# Serial_CAN_Bus_V1_1.net
KiCad netlist of a schematic drawn in EAGLE
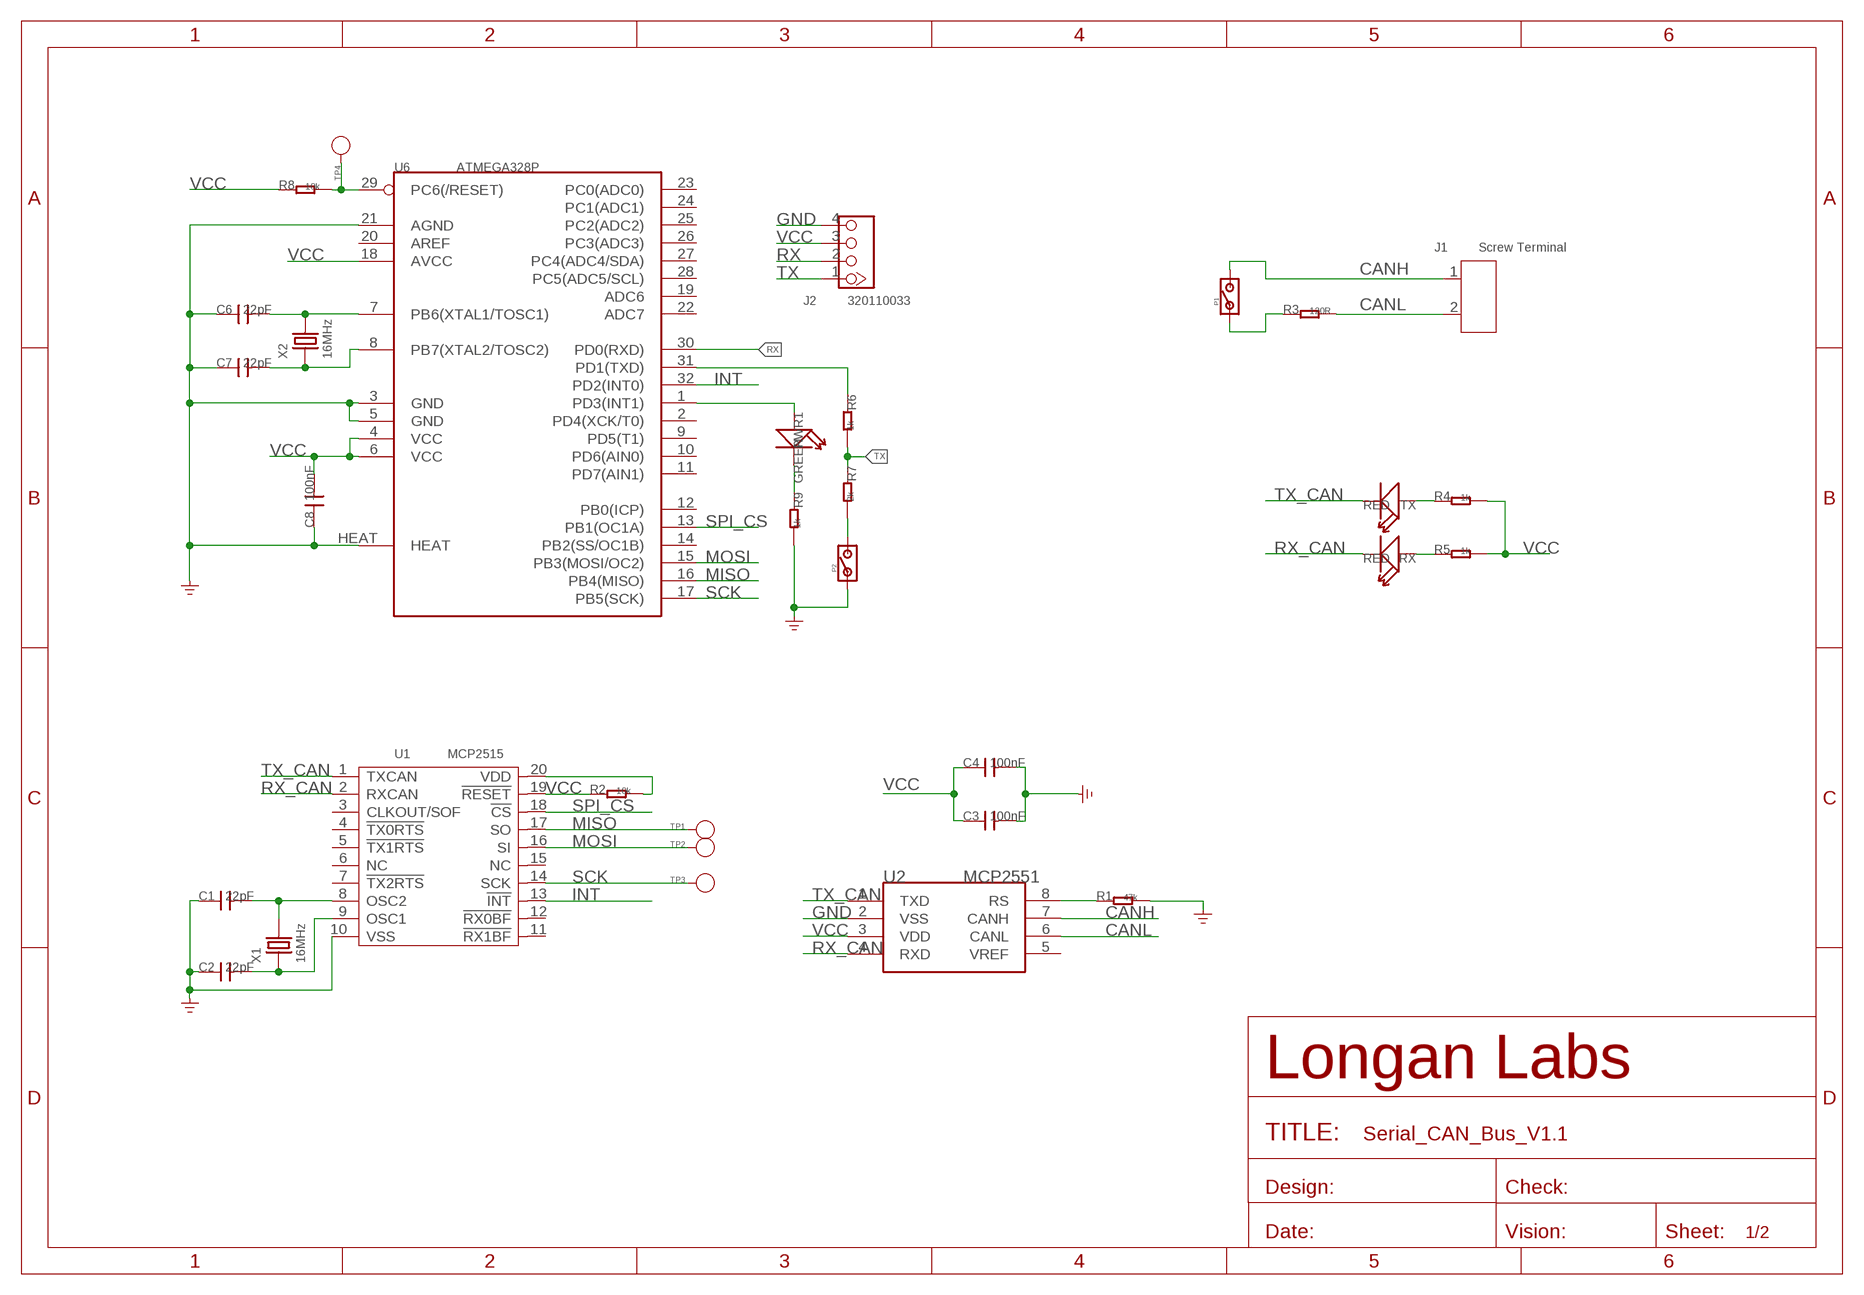
[diagram p0: schematic, sheet 1]

(export (version "E")
  (design (tool "Eeschema 10.0.6"))
  (components
    (comp (ref "C1")
      (value "22pF")
      (footprint "eagle-import:0603")
      (libsource (lib "eagle-import") (part "C-0603"))
    )
    (comp (ref "C2")
      (value "22pF")
      (footprint "eagle-import:0603")
      (libsource (lib "eagle-import") (part "C-0603"))
    )
    (comp (ref "C3")
      (value "100nF")
      (footprint "eagle-import:0603")
      (libsource (lib "eagle-import") (part "C-0603"))
    )
    (comp (ref "C4")
      (value "100nF")
      (footprint "eagle-import:0603")
      (libsource (lib "eagle-import") (part "C-0603"))
    )
    (comp (ref "C6")
      (value "22pF")
      (footprint "eagle-import:0603")
      (libsource (lib "eagle-import") (part "C-0603"))
    )
    (comp (ref "C7")
      (value "22pF")
      (footprint "eagle-import:0603")
      (libsource (lib "eagle-import") (part "C-0603"))
    )
    (comp (ref "C8")
      (value "100nF")
      (footprint "eagle-import:0603")
      (libsource (lib "eagle-import") (part "C-0603"))
    )
    (comp (ref "J1")
      (value "Screw Terminal")
      (footprint "eagle-import:2P-3.5")
      (libsource (lib "eagle-import") (part "SCREW-TERMINAL-2P'3.5'"))
    )
    (comp (ref "J2")
      (value "320110033")
      (footprint "eagle-import:HW4-2.0")
      (libsource (lib "eagle-import") (part "GROVE-CONNECTOR-DIP-2.0"))
    )
    (comp (ref "P1")
      (value "PAD-JUMPER-2P")
      (footprint "eagle-import:2P-SMD-1.78X1.27")
      (libsource (lib "eagle-import") (part "PAD-JUMPER-2P"))
    )
    (comp (ref "P2")
      (value "PAD-JUMPER-2P")
      (footprint "eagle-import:2P-SMD-1.78X1.27")
      (libsource (lib "eagle-import") (part "PAD-JUMPER-2P"))
    )
    (comp (ref "PWR1")
      (value "GREEN")
      (footprint "eagle-import:LED-0603")
      (libsource (lib "eagle-import") (part "LED'0603'"))
    )
    (comp (ref "R1")
      (value "47k")
      (footprint "eagle-import:0603")
      (libsource (lib "eagle-import") (part "R-0603"))
    )
    (comp (ref "R2")
      (value "10k")
      (footprint "eagle-import:0603")
      (libsource (lib "eagle-import") (part "R-0603"))
    )
    (comp (ref "R3")
      (value "120R")
      (footprint "eagle-import:0603")
      (libsource (lib "eagle-import") (part "R-0603"))
    )
    (comp (ref "R4")
      (value "1k")
      (footprint "eagle-import:0603")
      (libsource (lib "eagle-import") (part "R-0603"))
    )
    (comp (ref "R5")
      (value "1k")
      (footprint "eagle-import:0603")
      (libsource (lib "eagle-import") (part "R-0603"))
    )
    (comp (ref "R6")
      (value "1k")
      (footprint "eagle-import:0603")
      (libsource (lib "eagle-import") (part "R-0603"))
    )
    (comp (ref "R7")
      (value "2k")
      (footprint "eagle-import:0603")
      (libsource (lib "eagle-import") (part "R-0603"))
    )
    (comp (ref "R8")
      (value "10k")
      (footprint "eagle-import:0603")
      (libsource (lib "eagle-import") (part "R-0603"))
    )
    (comp (ref "R9")
      (value "1k")
      (footprint "eagle-import:0603")
      (libsource (lib "eagle-import") (part "R-0603"))
    )
    (comp (ref "RX")
      (value "RED")
      (footprint "eagle-import:LED-0603")
      (libsource (lib "eagle-import") (part "LED'0603'"))
    )
    (comp (ref "TP1")
      (value "PAD-TEST-POINT'4545'")
      (footprint "eagle-import:TP_4545")
      (fields (field (name "PARTNO") "DNP"))
      (libsource (lib "eagle-import") (part "PAD-TEST-POINT'4545'"))
    )
    (comp (ref "TP2")
      (value "PAD-TEST-POINT'4545'")
      (footprint "eagle-import:TP_4545")
      (fields (field (name "PARTNO") "DNP"))
      (libsource (lib "eagle-import") (part "PAD-TEST-POINT'4545'"))
    )
    (comp (ref "TP3")
      (value "PAD-TEST-POINT'4545'")
      (footprint "eagle-import:TP_4545")
      (fields (field (name "PARTNO") "DNP"))
      (libsource (lib "eagle-import") (part "PAD-TEST-POINT'4545'"))
    )
    (comp (ref "TP4")
      (value "PAD-TEST-POINT'4545'")
      (footprint "eagle-import:TP_4545")
      (fields (field (name "PARTNO") "DNP"))
      (libsource (lib "eagle-import") (part "PAD-TEST-POINT'4545'"))
    )
    (comp (ref "TX")
      (value "RED")
      (footprint "eagle-import:LED-0603")
      (libsource (lib "eagle-import") (part "LED'0603'"))
    )
    (comp (ref "U1")
      (value "MCP2515")
      (footprint "eagle-import:TSSOP20-0.65-6.5X4.4MM")
      (libsource (lib "eagle-import") (part "MCP2515'ST'"))
    )
    (comp (ref "U2")
      (value "MCP2551")
      (footprint "eagle-import:SOIC8-6.0")
      (libsource (lib "eagle-import") (part "MCP2551-SOIC8"))
    )
    (comp (ref "U6")
      (value "ATMEGA328P")
      (footprint "eagle-import:MLF32X")
      (libsource (lib "eagle-import") (part "MEGA8"))
    )
    (comp (ref "X1")
      (value "16MHz")
      (footprint "eagle-import:X2-SMD-5.0X3.2X1.3MM")
      (libsource (lib "eagle-import") (part "CRYSTAL-2P'5032'"))
    )
    (comp (ref "X2")
      (value "16MHz")
      (footprint "eagle-import:X2-SMD-5.0X3.2X1.3MM")
      (libsource (lib "eagle-import") (part "CRYSTAL-2P'5032'"))
    )
  )
  (nets
    (net (code "1") (name "CANH") (class "Default")
      (node (ref "J1") (pin "1") (pinfunction "1_1") (pintype "bidirectional"))
      (node (ref "P1") (pin "2") (pinfunction "2_2") (pintype "bidirectional"))
      (node (ref "U2") (pin "7") (pinfunction "CANH_7") (pintype "bidirectional"))
    )
    (net (code "2") (name "CANL") (class "Default")
      (node (ref "J1") (pin "2") (pinfunction "2_2") (pintype "bidirectional"))
      (node (ref "R3") (pin "2") (pinfunction "2_2") (pintype "passive"))
      (node (ref "U2") (pin "6") (pinfunction "CANL_6") (pintype "bidirectional"))
    )
    (net (code "3") (name "GND") (class "Default")
      (node (ref "C1") (pin "1") (pinfunction "1_1") (pintype "passive"))
      (node (ref "C2") (pin "1") (pinfunction "1_1") (pintype "passive"))
      (node (ref "C3") (pin "2") (pinfunction "2_2") (pintype "passive"))
      (node (ref "C4") (pin "2") (pinfunction "2_2") (pintype "passive"))
      (node (ref "C6") (pin "1") (pinfunction "1_1") (pintype "passive"))
      (node (ref "C7") (pin "1") (pinfunction "1_1") (pintype "passive"))
      (node (ref "C8") (pin "1") (pinfunction "1_1") (pintype "passive"))
      (node (ref "J2") (pin "4") (pinfunction "4_4") (pintype "bidirectional"))
      (node (ref "P2") (pin "1") (pinfunction "1_1") (pintype "bidirectional"))
      (node (ref "R1") (pin "2") (pinfunction "2_2") (pintype "passive"))
      (node (ref "R9") (pin "2") (pinfunction "2_2") (pintype "passive"))
      (node (ref "U1") (pin "10") (pinfunction "VSS_10") (pintype "bidirectional"))
      (node (ref "U2") (pin "2") (pinfunction "VSS_2") (pintype "bidirectional"))
      (node (ref "U6") (pin "21") (pinfunction "AGND_21") (pintype "bidirectional"))
      (node (ref "U6") (pin "3") (pinfunction "GND_3") (pintype "bidirectional"))
      (node (ref "U6") (pin "5") (pinfunction "GND_5") (pintype "bidirectional"))
      (node (ref "U6") (pin "HEAT") (pinfunction "HEAT_HEAT") (pintype "bidirectional"))
    )
    (net (code "4") (name "INT") (class "Default")
      (node (ref "U1") (pin "13") (pinfunction "~{INT}_13") (pintype "bidirectional"))
      (node (ref "U6") (pin "32") (pinfunction "PD2(INT0)_32") (pintype "bidirectional"))
    )
    (net (code "5") (name "MISO") (class "Default")
      (node (ref "TP1") (pin "T") (pinfunction "T_T") (pintype "bidirectional"))
      (node (ref "U1") (pin "17") (pinfunction "SO_17") (pintype "bidirectional"))
      (node (ref "U6") (pin "16") (pinfunction "PB4(MISO)_16") (pintype "bidirectional"))
    )
    (net (code "6") (name "MOSI") (class "Default")
      (node (ref "TP2") (pin "T") (pinfunction "T_T") (pintype "bidirectional"))
      (node (ref "U1") (pin "16") (pinfunction "SI_16") (pintype "bidirectional"))
      (node (ref "U6") (pin "15") (pinfunction "PB3(MOSI/OC2)_15") (pintype "bidirectional"))
    )
    (net (code "7") (name "Net-(P1-Pad1)") (class "Default")
      (node (ref "P1") (pin "1") (pinfunction "1_1") (pintype "bidirectional"))
      (node (ref "R3") (pin "1") (pinfunction "1_1") (pintype "passive"))
    )
    (net (code "8") (name "Net-(P2-Pad2)") (class "Default")
      (node (ref "P2") (pin "2") (pinfunction "2_2") (pintype "bidirectional"))
      (node (ref "R7") (pin "2") (pinfunction "2_2") (pintype "passive"))
    )
    (net (code "9") (name "Net-(PWR1-Pad-)") (class "Default")
      (node (ref "PWR1") (pin "-") (pinfunction "-_-") (pintype "passive"))
      (node (ref "R9") (pin "1") (pinfunction "1_1") (pintype "passive"))
    )
    (net (code "10") (name "Net-(R4-Pad1)") (class "Default")
      (node (ref "R4") (pin "1") (pinfunction "1_1") (pintype "passive"))
      (node (ref "TX") (pin "+") (pinfunction "+_+") (pintype "passive"))
    )
    (net (code "11") (name "Net-(R5-Pad1)") (class "Default")
      (node (ref "R5") (pin "1") (pinfunction "1_1") (pintype "passive"))
      (node (ref "RX") (pin "+") (pinfunction "+_+") (pintype "passive"))
    )
    (net (code "12") (name "Net-(U1-OSC1)") (class "Default")
      (node (ref "C2") (pin "2") (pinfunction "2_2") (pintype "passive"))
      (node (ref "U1") (pin "9") (pinfunction "OSC1_9") (pintype "bidirectional"))
      (node (ref "X1") (pin "1") (pinfunction "1_1") (pintype "passive"))
    )
    (net (code "13") (name "Net-(U1-OSC2)") (class "Default")
      (node (ref "C1") (pin "2") (pinfunction "2_2") (pintype "passive"))
      (node (ref "U1") (pin "8") (pinfunction "OSC2_8") (pintype "bidirectional"))
      (node (ref "X1") (pin "2") (pinfunction "2_2") (pintype "passive"))
    )
    (net (code "14") (name "Net-(U1-~{RESET})") (class "Default")
      (node (ref "R2") (pin "1") (pinfunction "1_1") (pintype "passive"))
      (node (ref "U1") (pin "19") (pinfunction "~{RESET}_19") (pintype "bidirectional"))
    )
    (net (code "15") (name "Net-(U2-RS)") (class "Default")
      (node (ref "R1") (pin "1") (pinfunction "1_1") (pintype "passive"))
      (node (ref "U2") (pin "8") (pinfunction "RS_8") (pintype "bidirectional"))
    )
    (net (code "16") (name "Net-(U6-PB6(XTAL1{slash}TOSC1))") (class "Default")
      (node (ref "C6") (pin "2") (pinfunction "2_2") (pintype "passive"))
      (node (ref "U6") (pin "7") (pinfunction "PB6(XTAL1/TOSC1)_7") (pintype "bidirectional"))
      (node (ref "X2") (pin "2") (pinfunction "2_2") (pintype "passive"))
    )
    (net (code "17") (name "Net-(U6-PB7(XTAL2{slash}TOSC2))") (class "Default")
      (node (ref "C7") (pin "2") (pinfunction "2_2") (pintype "passive"))
      (node (ref "U6") (pin "8") (pinfunction "PB7(XTAL2/TOSC2)_8") (pintype "bidirectional"))
      (node (ref "X2") (pin "1") (pinfunction "1_1") (pintype "passive"))
    )
    (net (code "18") (name "Net-(U6-PC6({slash}RESET))") (class "Default")
      (node (ref "R8") (pin "2") (pinfunction "2_2") (pintype "passive"))
      (node (ref "TP4") (pin "T") (pinfunction "T_T") (pintype "bidirectional"))
      (node (ref "U6") (pin "29") (pinfunction "PC6(/RESET)_29") (pintype "bidirectional"))
    )
    (net (code "19") (name "Net-(U6-PD1(TXD))") (class "Default")
      (node (ref "R6") (pin "1") (pinfunction "1_1") (pintype "passive"))
      (node (ref "U6") (pin "31") (pinfunction "PD1(TXD)_31") (pintype "bidirectional"))
    )
    (net (code "20") (name "Net-(U6-PD3(INT1))") (class "Default")
      (node (ref "PWR1") (pin "+") (pinfunction "+_+") (pintype "passive"))
      (node (ref "U6") (pin "1") (pinfunction "PD3(INT1)_1") (pintype "bidirectional"))
    )
    (net (code "21") (name "RX") (class "Default")
      (node (ref "J2") (pin "2") (pinfunction "2_2") (pintype "bidirectional"))
      (node (ref "U6") (pin "30") (pinfunction "PD0(RXD)_30") (pintype "bidirectional"))
    )
    (net (code "22") (name "RX_CAN") (class "Default")
      (node (ref "RX") (pin "-") (pinfunction "-_-") (pintype "passive"))
      (node (ref "U1") (pin "2") (pinfunction "RXCAN_2") (pintype "bidirectional"))
      (node (ref "U2") (pin "4") (pinfunction "RXD_4") (pintype "bidirectional"))
    )
    (net (code "23") (name "SCK") (class "Default")
      (node (ref "TP3") (pin "T") (pinfunction "T_T") (pintype "bidirectional"))
      (node (ref "U1") (pin "14") (pinfunction "SCK_14") (pintype "bidirectional"))
      (node (ref "U6") (pin "17") (pinfunction "PB5(SCK)_17") (pintype "bidirectional"))
    )
    (net (code "24") (name "SPI_CS") (class "Default")
      (node (ref "U1") (pin "18") (pinfunction "~{CS}_18") (pintype "bidirectional"))
      (node (ref "U6") (pin "13") (pinfunction "PB1(OC1A)_13") (pintype "bidirectional"))
    )
    (net (code "25") (name "TX") (class "Default")
      (node (ref "J2") (pin "1") (pinfunction "1_1") (pintype "bidirectional"))
      (node (ref "R6") (pin "2") (pinfunction "2_2") (pintype "passive"))
      (node (ref "R7") (pin "1") (pinfunction "1_1") (pintype "passive"))
    )
    (net (code "26") (name "TX_CAN") (class "Default")
      (node (ref "TX") (pin "-") (pinfunction "-_-") (pintype "passive"))
      (node (ref "U1") (pin "1") (pinfunction "TXCAN_1") (pintype "bidirectional"))
      (node (ref "U2") (pin "1") (pinfunction "TXD_1") (pintype "bidirectional"))
    )
    (net (code "27") (name "VCC") (class "Default")
      (node (ref "C3") (pin "1") (pinfunction "1_1") (pintype "passive"))
      (node (ref "C4") (pin "1") (pinfunction "1_1") (pintype "passive"))
      (node (ref "C8") (pin "2") (pinfunction "2_2") (pintype "passive"))
      (node (ref "J2") (pin "3") (pinfunction "3_3") (pintype "bidirectional"))
      (node (ref "R2") (pin "2") (pinfunction "2_2") (pintype "passive"))
      (node (ref "R4") (pin "2") (pinfunction "2_2") (pintype "passive"))
      (node (ref "R5") (pin "2") (pinfunction "2_2") (pintype "passive"))
      (node (ref "R8") (pin "1") (pinfunction "1_1") (pintype "passive"))
      (node (ref "U1") (pin "20") (pinfunction "VDD_20") (pintype "bidirectional"))
      (node (ref "U2") (pin "3") (pinfunction "VDD_3") (pintype "bidirectional"))
      (node (ref "U6") (pin "18") (pinfunction "AVCC_18") (pintype "bidirectional"))
      (node (ref "U6") (pin "4") (pinfunction "VCC_4") (pintype "bidirectional"))
      (node (ref "U6") (pin "6") (pinfunction "VCC_6") (pintype "bidirectional"))
    )
    (net (code "28") (name "unconnected-(U1-CLKOUT{slash}SOF-Pad3)") (class "Default")
      (node (ref "U1") (pin "3") (pinfunction "CLKOUT/SOF_3") (pintype "bidirectional"))
    )
    (net (code "29") (name "unconnected-(U1-NC-Pad6)") (class "Default")
      (node (ref "U1") (pin "6") (pinfunction "NC_6") (pintype "bidirectional"))
    )
    (net (code "30") (name "unconnected-(U1-NC-Pad15)") (class "Default")
      (node (ref "U1") (pin "15") (pinfunction "NC_15") (pintype "bidirectional"))
    )
    (net (code "31") (name "unconnected-(U1-~{RX0BF}-Pad12)") (class "Default")
      (node (ref "U1") (pin "12") (pinfunction "~{RX0BF}_12") (pintype "bidirectional"))
    )
    (net (code "32") (name "unconnected-(U1-~{RX1BF}-Pad11)") (class "Default")
      (node (ref "U1") (pin "11") (pinfunction "~{RX1BF}_11") (pintype "bidirectional"))
    )
    (net (code "33") (name "unconnected-(U1-~{TX0RTS}-Pad4)") (class "Default")
      (node (ref "U1") (pin "4") (pinfunction "~{TX0RTS}_4") (pintype "bidirectional"))
    )
    (net (code "34") (name "unconnected-(U1-~{TX1RTS}-Pad5)") (class "Default")
      (node (ref "U1") (pin "5") (pinfunction "~{TX1RTS}_5") (pintype "bidirectional"))
    )
    (net (code "35") (name "unconnected-(U1-~{TX2RTS}-Pad7)") (class "Default")
      (node (ref "U1") (pin "7") (pinfunction "~{TX2RTS}_7") (pintype "bidirectional"))
    )
    (net (code "36") (name "unconnected-(U2-VREF-Pad5)") (class "Default")
      (node (ref "U2") (pin "5") (pinfunction "VREF_5") (pintype "bidirectional"))
    )
    (net (code "37") (name "unconnected-(U6-ADC6-Pad19)") (class "Default")
      (node (ref "U6") (pin "19") (pinfunction "ADC6_19") (pintype "bidirectional"))
    )
    (net (code "38") (name "unconnected-(U6-ADC7-Pad22)") (class "Default")
      (node (ref "U6") (pin "22") (pinfunction "ADC7_22") (pintype "bidirectional"))
    )
    (net (code "39") (name "unconnected-(U6-AREF-Pad20)") (class "Default")
      (node (ref "U6") (pin "20") (pinfunction "AREF_20") (pintype "bidirectional"))
    )
    (net (code "40") (name "unconnected-(U6-PB0(ICP)-Pad12)") (class "Default")
      (node (ref "U6") (pin "12") (pinfunction "PB0(ICP)_12") (pintype "bidirectional"))
    )
    (net (code "41") (name "unconnected-(U6-PB2(SS{slash}OC1B)-Pad14)") (class "Default")
      (node (ref "U6") (pin "14") (pinfunction "PB2(SS/OC1B)_14") (pintype "bidirectional"))
    )
    (net (code "42") (name "unconnected-(U6-PC0(ADC0)-Pad23)") (class "Default")
      (node (ref "U6") (pin "23") (pinfunction "PC0(ADC0)_23") (pintype "bidirectional"))
    )
    (net (code "43") (name "unconnected-(U6-PC1(ADC1)-Pad24)") (class "Default")
      (node (ref "U6") (pin "24") (pinfunction "PC1(ADC1)_24") (pintype "bidirectional"))
    )
    (net (code "44") (name "unconnected-(U6-PC2(ADC2)-Pad25)") (class "Default")
      (node (ref "U6") (pin "25") (pinfunction "PC2(ADC2)_25") (pintype "bidirectional"))
    )
    (net (code "45") (name "unconnected-(U6-PC3(ADC3)-Pad26)") (class "Default")
      (node (ref "U6") (pin "26") (pinfunction "PC3(ADC3)_26") (pintype "bidirectional"))
    )
    (net (code "46") (name "unconnected-(U6-PC4(ADC4{slash}SDA)-Pad27)") (class "Default")
      (node (ref "U6") (pin "27") (pinfunction "PC4(ADC4/SDA)_27") (pintype "bidirectional"))
    )
    (net (code "47") (name "unconnected-(U6-PC5(ADC5{slash}SCL)-Pad28)") (class "Default")
      (node (ref "U6") (pin "28") (pinfunction "PC5(ADC5/SCL)_28") (pintype "bidirectional"))
    )
    (net (code "48") (name "unconnected-(U6-PD4(XCK{slash}T0)-Pad2)") (class "Default")
      (node (ref "U6") (pin "2") (pinfunction "PD4(XCK/T0)_2") (pintype "bidirectional"))
    )
    (net (code "49") (name "unconnected-(U6-PD5(T1)-Pad9)") (class "Default")
      (node (ref "U6") (pin "9") (pinfunction "PD5(T1)_9") (pintype "bidirectional"))
    )
    (net (code "50") (name "unconnected-(U6-PD6(AIN0)-Pad10)") (class "Default")
      (node (ref "U6") (pin "10") (pinfunction "PD6(AIN0)_10") (pintype "bidirectional"))
    )
    (net (code "51") (name "unconnected-(U6-PD7(AIN1)-Pad11)") (class "Default")
      (node (ref "U6") (pin "11") (pinfunction "PD7(AIN1)_11") (pintype "bidirectional"))
    )
  )
)
